# Boost_Converter_6V.net
KiCad netlist of a schematic drawn in Altium Designer
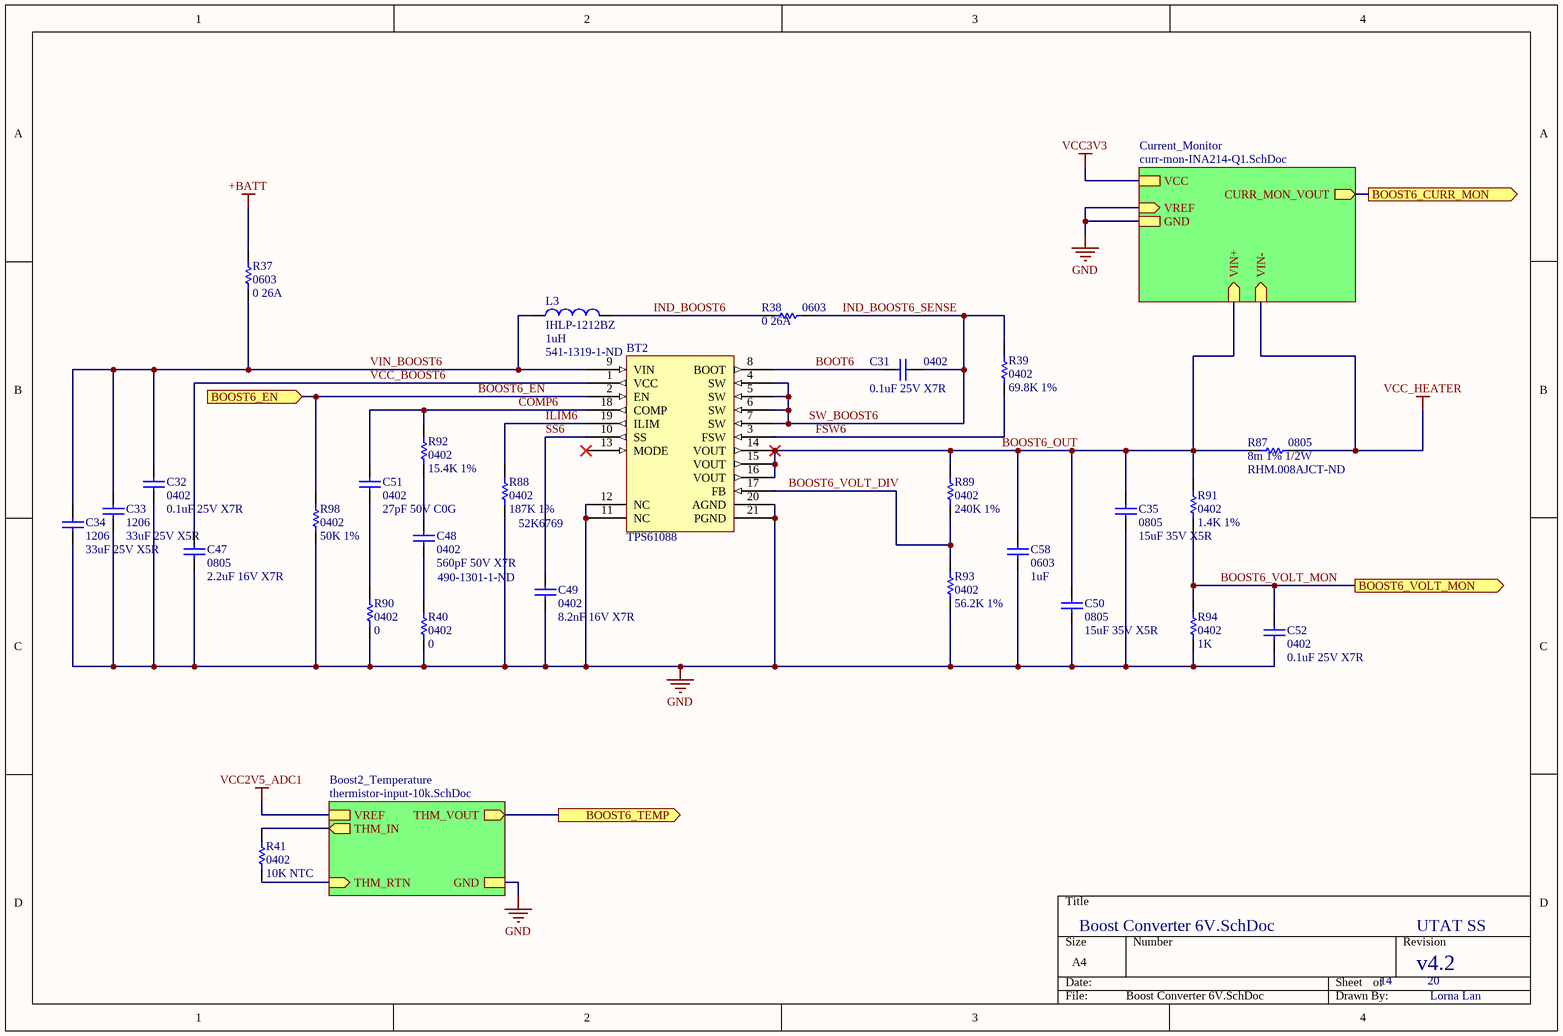
[diagram p0: Boost Converter 6V.SchDoc]

(export (version "E")
  (design (tool "Eeschema 10.0.6"))
  (components
    (comp (ref "BT2")
      (value "TPS61088")
      (footprint "QFN50P450X350X100-21N")
      (description "Boost converter")
      (libsource (lib "EPS") (part "TPS61088"))
    )
    (comp (ref "C31")
      (value "0402")
      (footprint "CAP0402R")
      (description "0402 capacitor")
      (fields (field (name "ALTIUM_VALUE") "0.1uF 25V X7R"))
      (libsource (lib "heron-general") (part "CAP0402"))
    )
    (comp (ref "C32")
      (value "0402")
      (footprint "CAP0402R")
      (description "0402 capacitor")
      (fields (field (name "ALTIUM_VALUE") "0.1uF 25V X7R"))
      (libsource (lib "heron-general") (part "CAP0402"))
    )
    (comp (ref "C33")
      (value "1206")
      (footprint "CAP1206R")
      (description "1206 capacitor")
      (fields (field (name "ALTIUM_VALUE") "33uF 25V X5R"))
      (libsource (lib "heron-general") (part "CAP1206"))
    )
    (comp (ref "C34")
      (value "1206")
      (footprint "CAP1206R")
      (description "1206 capacitor")
      (fields (field (name "ALTIUM_VALUE") "33uF 25V X5R"))
      (libsource (lib "heron-general") (part "CAP1206"))
    )
    (comp (ref "C35")
      (value "0805")
      (footprint "CAP0805R")
      (description "0805 capacitor")
      (fields (field (name "ALTIUM_VALUE") "15uF 35V X5R"))
      (libsource (lib "heron-general") (part "CAP0805"))
    )
    (comp (ref "C47")
      (value "0805")
      (footprint "CAP0805R")
      (description "0805 capacitor")
      (fields (field (name "ALTIUM_VALUE") "2.2uF 16V X7R"))
      (libsource (lib "heron-general") (part "CAP0805"))
    )
    (comp (ref "C48")
      (value "0402")
      (footprint "CAP0402R")
      (description "0402 capacitor")
      (fields
        (field (name "ALTIUM_VALUE") "560pF 50V X7R")
        (field (name "SUPPLIER PART NUMBER 1") "490-1301-1-ND")
      )
      (libsource (lib "heron-general") (part "CAP0402"))
    )
    (comp (ref "C49")
      (value "0402")
      (footprint "CAP0402R")
      (description "0402 capacitor")
      (fields (field (name "ALTIUM_VALUE") "8.2nF 16V X7R"))
      (libsource (lib "CAP0402") (part "CAP0402"))
    )
    (comp (ref "C50")
      (value "0805")
      (footprint "CAP0805R")
      (description "0805 capacitor")
      (fields (field (name "ALTIUM_VALUE") "15uF 35V X5R"))
      (libsource (lib "heron-general") (part "CAP0805"))
    )
    (comp (ref "C51")
      (value "0402")
      (footprint "CAP0402R")
      (description "0402 capacitor")
      (fields (field (name "ALTIUM_VALUE") "27pF 50V C0G"))
      (libsource (lib "heron-general") (part "CAP0402"))
    )
    (comp (ref "C52")
      (value "0402")
      (footprint "CAP0402R")
      (description "0402 capacitor")
      (fields (field (name "ALTIUM_VALUE") "0.1uF 25V X7R"))
      (libsource (lib "heron-general") (part "CAP0402"))
    )
    (comp (ref "C58")
      (value "0603")
      (footprint "CAP0603R")
      (description "0603 capacitor")
      (fields
        (field (name "ALTIUM_VALUE") "1uF")
        (field (name "MANUFACTURER") "KEMET")
        (field (name "MANUFACTURER PART NUMBER") "C0603C105K4RACAUTO")
      )
      (libsource (lib "heron-general") (part "CAP0603"))
    )
    (comp (ref "L3")
      (value "IHLP-1212BZ")
      (footprint "IHLP-1212BZ")
      (description "1µH Shielded Molded Inductor 5A 24mOhm Max Nonstandard")
      (fields
        (field (name "MANUFACTURER") "Vishay Dale")
        (field (name "MANUFACTURER PART NUMBER") "IHLP1212BZER1R0M11")
        (field (name "INDUCTANCE") "1uH")
        (field (name "SUPPLIER PART NUMBER 1") "541-1319-1-ND")
      )
      (libsource (lib "heron-general") (part "IND_IHLP-1212BZ"))
    )
    (comp (ref "R37")
      (value "0603")
      (footprint "RES0603R")
      (description "0603 resistor")
      (fields (field (name "ALTIUM_VALUE") "0 26A"))
      (libsource (lib "heron-general") (part "RES0603"))
    )
    (comp (ref "R38")
      (value "0603")
      (footprint "RES0603R")
      (description "0603 resistor")
      (fields (field (name "ALTIUM_VALUE") "0 26A"))
      (libsource (lib "heron-general") (part "RES0603"))
    )
    (comp (ref "R39")
      (value "0402")
      (footprint "RES0402R")
      (description "0402 resistor")
      (fields (field (name "ALTIUM_VALUE") "69.8K 1%"))
      (libsource (lib "heron-general") (part "RES0402"))
    )
    (comp (ref "R40")
      (value "0402")
      (footprint "RES0402R")
      (description "0402 resistor")
      (fields
        (field (name "ALTIUM_VALUE") "0")
        (field (name "MANUFACTURER") "Panasonic")
        (field (name "MANUFACTURER PART NUMBER") "ERJ-2GE0R00X")
      )
      (libsource (lib "heron-general") (part "RES0402"))
    )
    (comp (ref "R41")
      (value "0402")
      (footprint "RES0402R")
      (description "0402 resistor")
      (fields (field (name "ALTIUM_VALUE") "10K NTC"))
      (libsource (lib "heron-general") (part "RES0402"))
    )
    (comp (ref "R87")
      (value "0805")
      (footprint "RES0805R")
      (description "0805 resistor")
      (fields
        (field (name "ALTIUM_VALUE") "8m 1% 1/2W")
        (field (name "SUPPLIER PART NUMBER 1") "RHM.008AJCT-ND")
      )
      (libsource (lib "RES0805") (part "RES0805"))
    )
    (comp (ref "R88")
      (value "0402")
      (footprint "RES0402R")
      (description "0402 resistor")
      (fields (field (name "ALTIUM_VALUE") "187K 1%") (field (name "SUPPLIER PART NUMBER 1") "52K6769"))
      (libsource (lib "heron-general") (part "RES0402"))
    )
    (comp (ref "R89")
      (value "0402")
      (footprint "RES0402R")
      (description "0402 resistor")
      (fields (field (name "ALTIUM_VALUE") "240K 1%"))
      (libsource (lib "RES0402") (part "RES0402"))
    )
    (comp (ref "R90")
      (value "0402")
      (footprint "RES0402R")
      (description "0402 resistor")
      (fields
        (field (name "ALTIUM_VALUE") "0")
        (field (name "MANUFACTURER") "Panasonic")
        (field (name "MANUFACTURER PART NUMBER") "ERJ-2GE0R00X")
      )
      (libsource (lib "heron-general") (part "RES0402"))
    )
    (comp (ref "R91")
      (value "0402")
      (footprint "RES0402R")
      (description "0402 resistor")
      (fields (field (name "ALTIUM_VALUE") "1.4K 1%"))
      (libsource (lib "RES0402") (part "RES0402"))
    )
    (comp (ref "R92")
      (value "0402")
      (footprint "RES0402R")
      (description "0402 resistor")
      (fields (field (name "ALTIUM_VALUE") "15.4K 1%"))
      (libsource (lib "heron-general") (part "RES0402"))
    )
    (comp (ref "R93")
      (value "0402")
      (footprint "RES0402R")
      (description "0402 resistor")
      (fields (field (name "ALTIUM_VALUE") "56.2K 1%"))
      (libsource (lib "RES0402") (part "RES0402"))
    )
    (comp (ref "R94")
      (value "0402")
      (footprint "RES0402R")
      (description "0402 resistor")
      (fields (field (name "ALTIUM_VALUE") "1K"))
      (libsource (lib "RES0402") (part "RES0402"))
    )
    (comp (ref "R98")
      (value "0402")
      (footprint "RES0402R")
      (description "0402 resistor")
      (fields (field (name "ALTIUM_VALUE") "50K 1%"))
      (libsource (lib "heron-general") (part "RES0402"))
    )
  )
  (nets
    (net (code "1") (name "+BATT") (class "Default")
      (node (ref "R37") (pin "2") (pinfunction "2_2") (pintype "passive"))
    )
    (net (code "3") (name "/BOOST6_EN") (class "Default")
      (node (ref "BT2") (pin "2") (pinfunction "EN_2") (pintype "input"))
      (node (ref "R98") (pin "2") (pinfunction "2_2") (pintype "passive"))
    )
    (net (code "4") (name "/BOOST6_OUT") (class "Default")
      (node (ref "BT2") (pin "14") (pinfunction "VOUT_14") (pintype "output"))
      (node (ref "BT2") (pin "15") (pinfunction "VOUT_15") (pintype "output"))
      (node (ref "BT2") (pin "16") (pinfunction "VOUT_16") (pintype "output"))
      (node (ref "C35") (pin "2") (pinfunction "2_2") (pintype "passive"))
      (node (ref "C50") (pin "2") (pinfunction "2_2") (pintype "passive"))
      (node (ref "C58") (pin "2") (pinfunction "2_2") (pintype "passive"))
      (node (ref "R87") (pin "1") (pinfunction "1_1") (pintype "passive"))
      (node (ref "R89") (pin "2") (pinfunction "2_2") (pintype "passive"))
      (node (ref "R91") (pin "2") (pinfunction "2_2") (pintype "passive"))
    )
    (net (code "6") (name "/BOOST6_VOLT_DIV") (class "Default")
      (node (ref "BT2") (pin "17") (pinfunction "FB_17") (pintype "input"))
      (node (ref "R89") (pin "1") (pinfunction "1_1") (pintype "passive"))
      (node (ref "R93") (pin "2") (pinfunction "2_2") (pintype "passive"))
    )
    (net (code "7") (name "/BOOST6_VOLT_MON") (class "Default")
      (node (ref "C52") (pin "2") (pinfunction "2_2") (pintype "passive"))
      (node (ref "R91") (pin "1") (pinfunction "1_1") (pintype "passive"))
      (node (ref "R94") (pin "2") (pinfunction "2_2") (pintype "passive"))
    )
    (net (code "8") (name "/BOOT6") (class "Default")
      (node (ref "BT2") (pin "8") (pinfunction "BOOT_8") (pintype "output"))
      (node (ref "C31") (pin "1") (pinfunction "1_1") (pintype "passive"))
    )
    (net (code "9") (name "/COMP6") (class "Default")
      (node (ref "BT2") (pin "18") (pinfunction "COMP_18") (pintype "output"))
      (node (ref "C51") (pin "2") (pinfunction "2_2") (pintype "passive"))
      (node (ref "R92") (pin "2") (pinfunction "2_2") (pintype "passive"))
    )
    (net (code "10") (name "/FSW6") (class "Default")
      (node (ref "BT2") (pin "3") (pinfunction "FSW_3") (pintype "input"))
      (node (ref "R39") (pin "1") (pinfunction "1_1") (pintype "passive"))
    )
    (net (code "11") (name "/ILIM6") (class "Default")
      (node (ref "BT2") (pin "19") (pinfunction "ILIM_19") (pintype "output"))
      (node (ref "R88") (pin "2") (pinfunction "2_2") (pintype "passive"))
    )
    (net (code "12") (name "/IND_BOOST6") (class "Default")
      (node (ref "L3") (pin "2") (pinfunction "2_2") (pintype "passive"))
      (node (ref "R38") (pin "1") (pinfunction "1_1") (pintype "passive"))
    )
    (net (code "13") (name "/IND_BOOST6_SENSE") (class "Default")
      (node (ref "BT2") (pin "4") (pinfunction "SW_4") (pintype "input"))
      (node (ref "BT2") (pin "5") (pinfunction "SW_5") (pintype "input"))
      (node (ref "BT2") (pin "6") (pinfunction "SW_6") (pintype "input"))
      (node (ref "BT2") (pin "7") (pinfunction "SW_7") (pintype "input"))
      (node (ref "C31") (pin "2") (pinfunction "2_2") (pintype "passive"))
      (node (ref "R38") (pin "2") (pinfunction "2_2") (pintype "passive"))
      (node (ref "R39") (pin "2") (pinfunction "2_2") (pintype "passive"))
    )
    (net (code "14") (name "/SS6") (class "Default")
      (node (ref "BT2") (pin "10") (pinfunction "SS_10") (pintype "output"))
      (node (ref "C49") (pin "2") (pinfunction "2_2") (pintype "passive"))
    )
    (net (code "15") (name "/THM_IN") (class "Default")
      (node (ref "R41") (pin "2") (pinfunction "2_2") (pintype "passive"))
    )
    (net (code "16") (name "/THM_RTN") (class "Default")
      (node (ref "R41") (pin "1") (pinfunction "1_1") (pintype "passive"))
    )
    (net (code "17") (name "/VCC_BOOST6") (class "Default")
      (node (ref "BT2") (pin "1") (pinfunction "VCC_1") (pintype "output"))
      (node (ref "C47") (pin "2") (pinfunction "2_2") (pintype "passive"))
    )
    (net (code "18") (name "/VIN_BOOST6") (class "Default")
      (node (ref "BT2") (pin "9") (pinfunction "VIN_9") (pintype "input"))
      (node (ref "C32") (pin "2") (pinfunction "2_2") (pintype "passive"))
      (node (ref "C33") (pin "2") (pinfunction "2_2") (pintype "passive"))
      (node (ref "C34") (pin "2") (pinfunction "2_2") (pintype "passive"))
      (node (ref "L3") (pin "1") (pinfunction "1_1") (pintype "passive"))
      (node (ref "R37") (pin "1") (pinfunction "1_1") (pintype "passive"))
    )
    (net (code "19") (name "GND") (class "Default")
      (node (ref "BT2") (pin "11") (pinfunction "NC_11") (pintype "passive"))
      (node (ref "BT2") (pin "12") (pinfunction "NC_12") (pintype "passive"))
      (node (ref "BT2") (pin "20") (pinfunction "AGND_20") (pintype "power_in"))
      (node (ref "BT2") (pin "21") (pinfunction "PGND_21") (pintype "power_in"))
      (node (ref "C32") (pin "1") (pinfunction "1_1") (pintype "passive"))
      (node (ref "C33") (pin "1") (pinfunction "1_1") (pintype "passive"))
      (node (ref "C34") (pin "1") (pinfunction "1_1") (pintype "passive"))
      (node (ref "C35") (pin "1") (pinfunction "1_1") (pintype "passive"))
      (node (ref "C47") (pin "1") (pinfunction "1_1") (pintype "passive"))
      (node (ref "C49") (pin "1") (pinfunction "1_1") (pintype "passive"))
      (node (ref "C50") (pin "1") (pinfunction "1_1") (pintype "passive"))
      (node (ref "C52") (pin "1") (pinfunction "1_1") (pintype "passive"))
      (node (ref "C58") (pin "1") (pinfunction "1_1") (pintype "passive"))
      (node (ref "R40") (pin "1") (pinfunction "1_1") (pintype "passive"))
      (node (ref "R88") (pin "1") (pinfunction "1_1") (pintype "passive"))
      (node (ref "R90") (pin "1") (pinfunction "1_1") (pintype "passive"))
      (node (ref "R93") (pin "1") (pinfunction "1_1") (pintype "passive"))
      (node (ref "R94") (pin "1") (pinfunction "1_1") (pintype "passive"))
      (node (ref "R98") (pin "1") (pinfunction "1_1") (pintype "passive"))
    )
    (net (code "20") (name "Net-(C48-Pad1)") (class "Default")
      (node (ref "C48") (pin "1") (pinfunction "1_1") (pintype "passive"))
      (node (ref "R40") (pin "2") (pinfunction "2_2") (pintype "passive"))
    )
    (net (code "21") (name "Net-(C48-Pad2)") (class "Default")
      (node (ref "C48") (pin "2") (pinfunction "2_2") (pintype "passive"))
      (node (ref "R92") (pin "1") (pinfunction "1_1") (pintype "passive"))
    )
    (net (code "22") (name "Net-(C51-Pad1)") (class "Default")
      (node (ref "C51") (pin "1") (pinfunction "1_1") (pintype "passive"))
      (node (ref "R90") (pin "2") (pinfunction "2_2") (pintype "passive"))
    )
    (net (code "25") (name "VCC_HEATER") (class "Default")
      (node (ref "R87") (pin "2") (pinfunction "2_2") (pintype "passive"))
    )
    (net (code "26") (name "unconnected-(BT2-MODE-Pad13)") (class "Default")
      (node (ref "BT2") (pin "13") (pinfunction "MODE_13") (pintype "input+no_connect"))
    )
  )
)
